# Schematic.net
KiCad netlist of a schematic drawn in EAGLE
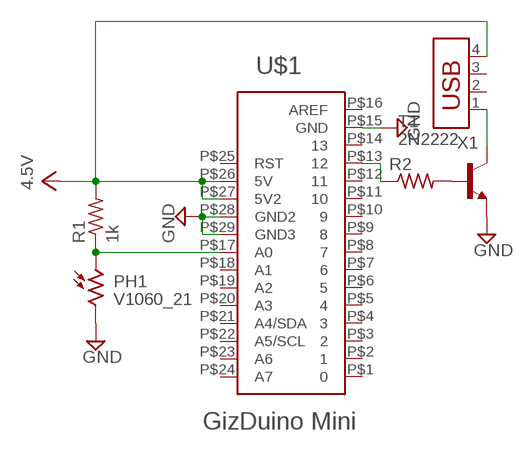
[diagram p0: schematic, sheet 1]

(export (version "E")
  (design (tool "Eeschema 10.0.6"))
  (components
    (comp (ref "PH1")
      (value "V1060_21")
      (footprint "eagle-import:TO-5_V10")
      (libsource (lib "eagle-import") (part "?1060V_21"))
    )
    (comp (ref "R1")
      (value "1k")
      (footprint "eagle-import:0207_7")
      (libsource (lib "eagle-import") (part "R-US_0207/7"))
    )
    (comp (ref "R2")
      (value "R-US_0204/7")
      (footprint "eagle-import:0204_7")
      (libsource (lib "eagle-import") (part "R-US_0204/7"))
    )
    (comp (ref "T1")
      (value "2N2222")
      (footprint "eagle-import:TO18")
      (libsource (lib "eagle-import") (part "2N2222"))
    )
    (comp (ref "U$1")
      (value "GIZDUINO-MINI")
      (footprint "eagle-import:GIZDUINO-MINI")
      (libsource (lib "eagle-import") (part "GIZDUINO-MINI"))
    )
    (comp (ref "X1")
      (value "USB-787616")
      (footprint "eagle-import:USB")
      (libsource (lib "eagle-import") (part "USB-787616"))
    )
  )
  (nets
    (net (code "1") (name "4.5V") (class "Default")
      (node (ref "R1") (pin "2") (pinfunction "2_2") (pintype "passive"))
      (node (ref "U$1") (pin "P$26") (pinfunction "5V_P$26") (pintype "bidirectional"))
      (node (ref "U$1") (pin "P$27") (pinfunction "5V2_P$27") (pintype "bidirectional"))
      (node (ref "X1") (pin "4") (pinfunction "4_4") (pintype "passive"))
    )
    (net (code "2") (name "GND") (class "Default")
      (node (ref "PH1") (pin "2") (pinfunction "2_2") (pintype "passive"))
      (node (ref "T1") (pin "1") (pinfunction "E_1") (pintype "passive"))
      (node (ref "U$1") (pin "P$15") (pinfunction "GND_P$15") (pintype "bidirectional"))
      (node (ref "U$1") (pin "P$28") (pinfunction "GND2_P$28") (pintype "bidirectional"))
      (node (ref "U$1") (pin "P$29") (pinfunction "GND3_P$29") (pintype "bidirectional"))
    )
    (net (code "3") (name "Net-(T1-B)") (class "Default")
      (node (ref "R2") (pin "2") (pinfunction "2_2") (pintype "passive"))
      (node (ref "T1") (pin "2") (pinfunction "B_2") (pintype "passive"))
    )
    (net (code "4") (name "Net-(T1-C)") (class "Default")
      (node (ref "T1") (pin "3") (pinfunction "C_3") (pintype "passive"))
      (node (ref "X1") (pin "1") (pinfunction "1_1") (pintype "passive"))
    )
    (net (code "5") (name "Net-(U$1-12)") (class "Default")
      (node (ref "R2") (pin "1") (pinfunction "1_1") (pintype "passive"))
      (node (ref "U$1") (pin "P$13") (pinfunction "12_P$13") (pintype "bidirectional"))
    )
    (net (code "6") (name "Net-(U$1-A0)") (class "Default")
      (node (ref "PH1") (pin "1") (pinfunction "1_1") (pintype "passive"))
      (node (ref "R1") (pin "1") (pinfunction "1_1") (pintype "passive"))
      (node (ref "U$1") (pin "P$17") (pinfunction "A0_P$17") (pintype "bidirectional"))
    )
    (net (code "7") (name "unconnected-(U$1-0-PadP$1)") (class "Default")
      (node (ref "U$1") (pin "P$1") (pinfunction "0_P$1") (pintype "bidirectional"))
    )
    (net (code "8") (name "unconnected-(U$1-1-PadP$2)") (class "Default")
      (node (ref "U$1") (pin "P$2") (pinfunction "1_P$2") (pintype "bidirectional"))
    )
    (net (code "9") (name "unconnected-(U$1-2-PadP$3)") (class "Default")
      (node (ref "U$1") (pin "P$3") (pinfunction "2_P$3") (pintype "bidirectional"))
    )
    (net (code "10") (name "unconnected-(U$1-3-PadP$4)") (class "Default")
      (node (ref "U$1") (pin "P$4") (pinfunction "3_P$4") (pintype "bidirectional"))
    )
    (net (code "11") (name "unconnected-(U$1-4-PadP$5)") (class "Default")
      (node (ref "U$1") (pin "P$5") (pinfunction "4_P$5") (pintype "bidirectional"))
    )
    (net (code "12") (name "unconnected-(U$1-5-PadP$6)") (class "Default")
      (node (ref "U$1") (pin "P$6") (pinfunction "5_P$6") (pintype "bidirectional"))
    )
    (net (code "13") (name "unconnected-(U$1-6-PadP$7)") (class "Default")
      (node (ref "U$1") (pin "P$7") (pinfunction "6_P$7") (pintype "bidirectional"))
    )
    (net (code "14") (name "unconnected-(U$1-7-PadP$8)") (class "Default")
      (node (ref "U$1") (pin "P$8") (pinfunction "7_P$8") (pintype "bidirectional"))
    )
    (net (code "15") (name "unconnected-(U$1-8-PadP$9)") (class "Default")
      (node (ref "U$1") (pin "P$9") (pinfunction "8_P$9") (pintype "bidirectional"))
    )
    (net (code "16") (name "unconnected-(U$1-9-PadP$10)") (class "Default")
      (node (ref "U$1") (pin "P$10") (pinfunction "9_P$10") (pintype "bidirectional"))
    )
    (net (code "17") (name "unconnected-(U$1-10-PadP$11)") (class "Default")
      (node (ref "U$1") (pin "P$11") (pinfunction "10_P$11") (pintype "bidirectional"))
    )
    (net (code "18") (name "unconnected-(U$1-11-PadP$12)") (class "Default")
      (node (ref "U$1") (pin "P$12") (pinfunction "11_P$12") (pintype "bidirectional"))
    )
    (net (code "19") (name "unconnected-(U$1-13-PadP$14)") (class "Default")
      (node (ref "U$1") (pin "P$14") (pinfunction "13_P$14") (pintype "bidirectional"))
    )
    (net (code "20") (name "unconnected-(U$1-A1-PadP$18)") (class "Default")
      (node (ref "U$1") (pin "P$18") (pinfunction "A1_P$18") (pintype "bidirectional"))
    )
    (net (code "21") (name "unconnected-(U$1-A2-PadP$19)") (class "Default")
      (node (ref "U$1") (pin "P$19") (pinfunction "A2_P$19") (pintype "bidirectional"))
    )
    (net (code "22") (name "unconnected-(U$1-A3-PadP$20)") (class "Default")
      (node (ref "U$1") (pin "P$20") (pinfunction "A3_P$20") (pintype "bidirectional"))
    )
    (net (code "23") (name "unconnected-(U$1-A4{slash}SDA-PadP$21)") (class "Default")
      (node (ref "U$1") (pin "P$21") (pinfunction "A4/SDA_P$21") (pintype "bidirectional"))
    )
    (net (code "24") (name "unconnected-(U$1-A5{slash}SCL-PadP$22)") (class "Default")
      (node (ref "U$1") (pin "P$22") (pinfunction "A5/SCL_P$22") (pintype "bidirectional"))
    )
    (net (code "25") (name "unconnected-(U$1-A6-PadP$23)") (class "Default")
      (node (ref "U$1") (pin "P$23") (pinfunction "A6_P$23") (pintype "bidirectional"))
    )
    (net (code "26") (name "unconnected-(U$1-A7-PadP$24)") (class "Default")
      (node (ref "U$1") (pin "P$24") (pinfunction "A7_P$24") (pintype "bidirectional"))
    )
    (net (code "27") (name "unconnected-(U$1-AREF-PadP$16)") (class "Default")
      (node (ref "U$1") (pin "P$16") (pinfunction "AREF_P$16") (pintype "bidirectional"))
    )
    (net (code "28") (name "unconnected-(U$1-RST-PadP$25)") (class "Default")
      (node (ref "U$1") (pin "P$25") (pinfunction "RST_P$25") (pintype "bidirectional"))
    )
    (net (code "29") (name "unconnected-(X1-Pad2)") (class "Default")
      (node (ref "X1") (pin "2") (pinfunction "2_2") (pintype "passive"))
    )
    (net (code "30") (name "unconnected-(X1-Pad3)") (class "Default")
      (node (ref "X1") (pin "3") (pinfunction "3_3") (pintype "passive"))
    )
  )
)
